# pc_ads1292r_brk_v3.net
KiCad netlist of a schematic drawn in EAGLE
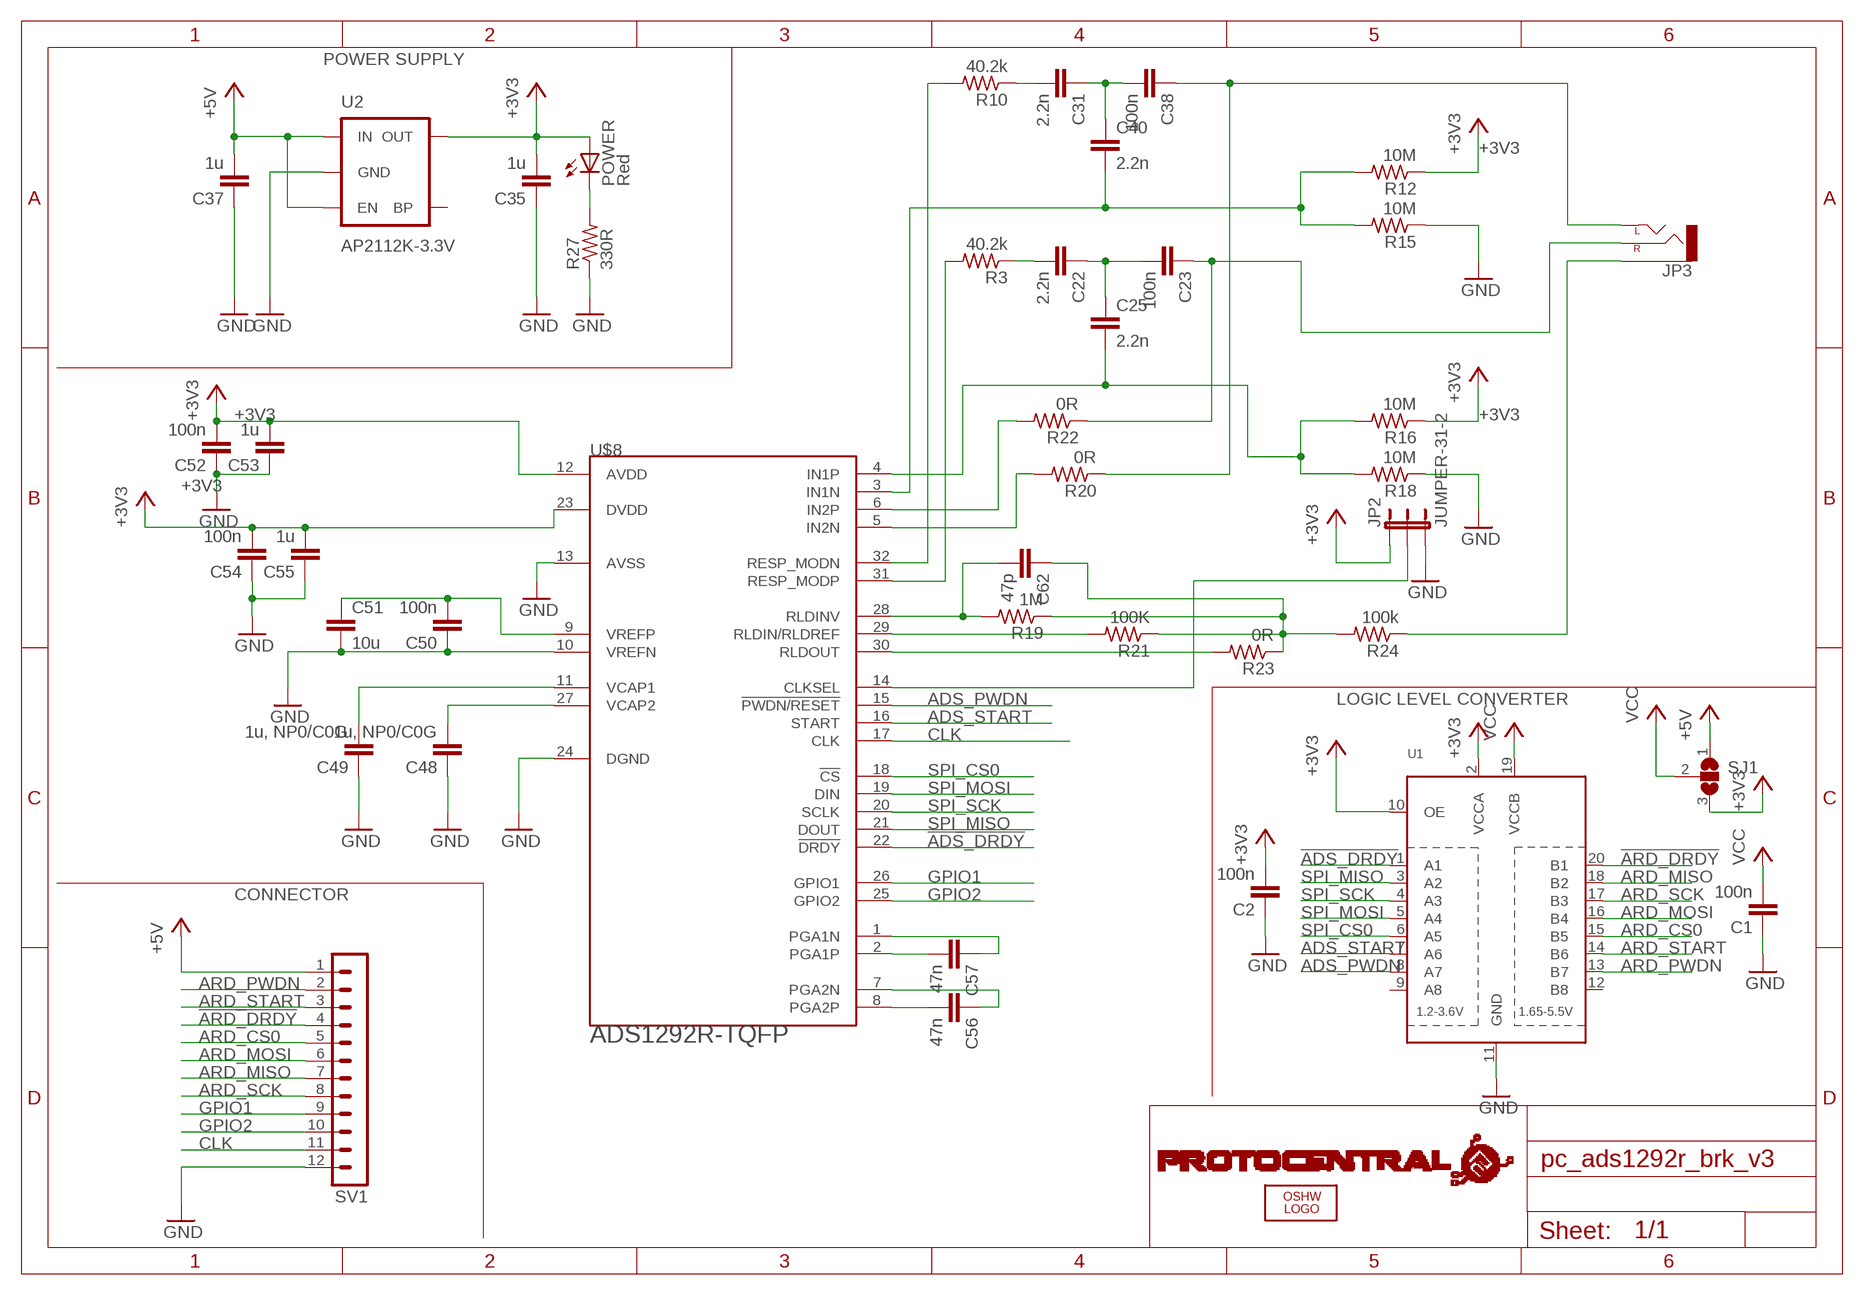
[diagram p0: schematic, sheet 1]

(export (version "E")
  (design (tool "Eeschema 10.0.6"))
  (components
    (comp (ref "C1")
      (value "100n")
      (footprint "eagle-import:C0402")
      (libsource (lib "eagle-import") (part "C-EUC0402"))
    )
    (comp (ref "C2")
      (value "100n")
      (footprint "eagle-import:C0402")
      (libsource (lib "eagle-import") (part "C-EUC0402"))
    )
    (comp (ref "C22")
      (value "2.2n")
      (footprint "eagle-import:C0402")
      (libsource (lib "eagle-import") (part "C-EUC0402"))
    )
    (comp (ref "C23")
      (value "100n")
      (footprint "eagle-import:C0402")
      (libsource (lib "eagle-import") (part "C-EUC0402"))
    )
    (comp (ref "C25")
      (value "2.2n")
      (footprint "eagle-import:C0402")
      (libsource (lib "eagle-import") (part "C-EUC0402"))
    )
    (comp (ref "C31")
      (value "2.2n")
      (footprint "eagle-import:C0402")
      (libsource (lib "eagle-import") (part "C-EUC0402"))
    )
    (comp (ref "C35")
      (value "1u")
      (footprint "eagle-import:C0402")
      (libsource (lib "eagle-import") (part "C-EUC0402"))
    )
    (comp (ref "C37")
      (value "1u")
      (footprint "eagle-import:C0402")
      (libsource (lib "eagle-import") (part "C-EUC0402"))
    )
    (comp (ref "C38")
      (value "100n")
      (footprint "eagle-import:C0402")
      (libsource (lib "eagle-import") (part "C-EUC0402"))
    )
    (comp (ref "C40")
      (value "2.2n")
      (footprint "eagle-import:C0402")
      (libsource (lib "eagle-import") (part "C-EUC0402"))
    )
    (comp (ref "C48")
      (value "1u, NP0/C0G")
      (footprint "eagle-import:C0402")
      (libsource (lib "eagle-import") (part "C-EUC0402"))
    )
    (comp (ref "C49")
      (value "1u, NP0/C0G")
      (footprint "eagle-import:C0402")
      (libsource (lib "eagle-import") (part "C-EUC0402"))
    )
    (comp (ref "C50")
      (value "100n")
      (footprint "eagle-import:C0402")
      (libsource (lib "eagle-import") (part "C-EUC0402"))
    )
    (comp (ref "C51")
      (value "10u")
      (footprint "eagle-import:C0603")
      (libsource (lib "eagle-import") (part "resistor_C-EUC0603"))
    )
    (comp (ref "C52")
      (value "100n")
      (footprint "eagle-import:C0402")
      (libsource (lib "eagle-import") (part "C-EUC0402"))
    )
    (comp (ref "C53")
      (value "1u")
      (footprint "eagle-import:C0402")
      (libsource (lib "eagle-import") (part "C-EUC0402"))
    )
    (comp (ref "C54")
      (value "100n")
      (footprint "eagle-import:C0402")
      (libsource (lib "eagle-import") (part "C-EUC0402"))
    )
    (comp (ref "C55")
      (value "1u")
      (footprint "eagle-import:C0402")
      (libsource (lib "eagle-import") (part "C-EUC0402"))
    )
    (comp (ref "C56")
      (value "47n")
      (footprint "eagle-import:C0402")
      (libsource (lib "eagle-import") (part "C-EUC0402"))
    )
    (comp (ref "C57")
      (value "47n")
      (footprint "eagle-import:C0402")
      (libsource (lib "eagle-import") (part "C-EUC0402"))
    )
    (comp (ref "C62")
      (value "47p")
      (footprint "eagle-import:C0402")
      (libsource (lib "eagle-import") (part "C-EUC0402"))
    )
    (comp (ref "JP2")
      (value "JUMPER-31-2")
      (footprint "eagle-import:SJ_3_PASTE1&2")
      (libsource (lib "eagle-import") (part "JUMPER-31-2"))
    )
    (comp (ref "JP3")
      (value "AUDIO-JACKSMD2")
      (footprint "eagle-import:AUDIO-JACK-3.5MM-SMD")
      (libsource (lib "eagle-import") (part "AUDIO-JACKSMD2"))
    )
    (comp (ref "LOGO1")
      (value "OSHW_LOGO_FILLX0100-NT")
      (footprint "eagle-import:OSHW_FILLX100_NOTEXT")
      (libsource (lib "eagle-import") (part "OSHW_LOGO_FILLX0100-NT"))
    )
    (comp (ref "POWER")
      (value "Red")
      (footprint "eagle-import:CHIPLED_0603")
      (libsource (lib "eagle-import") (part "LEDCHIPLED_0603"))
    )
    (comp (ref "R3")
      (value "40.2k")
      (footprint "eagle-import:R0402")
      (libsource (lib "eagle-import") (part "R-US_R0402"))
    )
    (comp (ref "R10")
      (value "40.2k")
      (footprint "eagle-import:R0402")
      (libsource (lib "eagle-import") (part "R-US_R0402"))
    )
    (comp (ref "R12")
      (value "10M")
      (footprint "eagle-import:R0402")
      (libsource (lib "eagle-import") (part "R-US_R0402"))
    )
    (comp (ref "R15")
      (value "10M")
      (footprint "eagle-import:R0402")
      (libsource (lib "eagle-import") (part "R-US_R0402"))
    )
    (comp (ref "R16")
      (value "10M")
      (footprint "eagle-import:R0402")
      (libsource (lib "eagle-import") (part "R-US_R0402"))
    )
    (comp (ref "R18")
      (value "10M")
      (footprint "eagle-import:R0402")
      (libsource (lib "eagle-import") (part "R-US_R0402"))
    )
    (comp (ref "R19")
      (value "1M")
      (footprint "eagle-import:R0402")
      (libsource (lib "eagle-import") (part "R-US_R0402"))
    )
    (comp (ref "R20")
      (value "0R")
      (footprint "eagle-import:R0402")
      (libsource (lib "eagle-import") (part "R-US_R0402"))
    )
    (comp (ref "R21")
      (value "100K")
      (footprint "eagle-import:R0402")
      (libsource (lib "eagle-import") (part "R-US_R0402"))
    )
    (comp (ref "R22")
      (value "0R")
      (footprint "eagle-import:R0402")
      (libsource (lib "eagle-import") (part "R-US_R0402"))
    )
    (comp (ref "R23")
      (value "0R")
      (footprint "eagle-import:R0402")
      (libsource (lib "eagle-import") (part "R-US_R0402"))
    )
    (comp (ref "R24")
      (value "100k")
      (footprint "eagle-import:R0402")
      (libsource (lib "eagle-import") (part "R-US_R0402"))
    )
    (comp (ref "R27")
      (value "330R")
      (footprint "eagle-import:R0402")
      (libsource (lib "eagle-import") (part "R-US_R0402"))
    )
    (comp (ref "SJ1")
      (value "SJ2W")
      (footprint "eagle-import:SJ_2")
      (libsource (lib "eagle-import") (part "SJ2W"))
    )
    (comp (ref "SV1")
      (value "MA12-1")
      (footprint "eagle-import:MA12-1")
      (libsource (lib "eagle-import") (part "MA12-1"))
    )
    (comp (ref "U$1")
      (value "PROTY-LOGO")
      (footprint "eagle-import:LOGO-PROTY")
      (libsource (lib "eagle-import") (part "PROTY-LOGO"))
    )
    (comp (ref "U$8")
      (value "ADS1292R-TQFP")
      (footprint "eagle-import:SQFP-S-5X5-32")
      (libsource (lib "eagle-import") (part "ADS1292R-TQFP"))
    )
    (comp (ref "U1")
      (value "TXB0108PWR")
      (footprint "eagle-import:TSSOP20")
      (libsource (lib "eagle-import") (part "TXB0108PWR"))
    )
    (comp (ref "U2")
      (value "AP2112K-3.3V")
      (footprint "eagle-import:SOT23-5")
      (libsource (lib "eagle-import") (part "V_REG_LDOSMD"))
    )
  )
  (nets
    (net (code "1") (name "+3V3") (class "Default")
      (node (ref "C2") (pin "2") (pinfunction "2_2") (pintype "passive"))
      (node (ref "C35") (pin "2") (pinfunction "2_2") (pintype "passive"))
      (node (ref "C52") (pin "2") (pinfunction "2_2") (pintype "passive"))
      (node (ref "C53") (pin "2") (pinfunction "2_2") (pintype "passive"))
      (node (ref "C54") (pin "2") (pinfunction "2_2") (pintype "passive"))
      (node (ref "C55") (pin "2") (pinfunction "2_2") (pintype "passive"))
      (node (ref "JP2") (pin "1") (pinfunction "1_1") (pintype "passive"))
      (node (ref "POWER") (pin "A") (pinfunction "A_A") (pintype "passive"))
      (node (ref "R12") (pin "1") (pinfunction "1_1") (pintype "passive"))
      (node (ref "R16") (pin "1") (pinfunction "1_1") (pintype "passive"))
      (node (ref "SJ1") (pin "3") (pinfunction "3_3") (pintype "passive"))
      (node (ref "U$8") (pin "12") (pinfunction "AVDD_12") (pintype "power_in"))
      (node (ref "U$8") (pin "23") (pinfunction "DVDD_23") (pintype "power_in"))
      (node (ref "U1") (pin "10") (pinfunction "OE_10") (pintype "bidirectional"))
      (node (ref "U1") (pin "2") (pinfunction "VCCA_2") (pintype "bidirectional"))
      (node (ref "U2") (pin "5") (pinfunction "OUT_5") (pintype "passive"))
    )
    (net (code "2") (name "+5V") (class "Default")
      (node (ref "C37") (pin "2") (pinfunction "2_2") (pintype "passive"))
      (node (ref "SJ1") (pin "1") (pinfunction "1_1") (pintype "passive"))
      (node (ref "SV1") (pin "1") (pinfunction "1_1") (pintype "passive"))
      (node (ref "U2") (pin "1") (pinfunction "IN_1") (pintype "input"))
      (node (ref "U2") (pin "3") (pinfunction "EN_3") (pintype "input"))
    )
    (net (code "3") (name "/ADS_PWDN") (class "Default")
      (node (ref "U$8") (pin "15") (pinfunction "~{PWDN/RESET}_15") (pintype "bidirectional"))
      (node (ref "U1") (pin "8") (pinfunction "A7_8") (pintype "bidirectional"))
    )
    (net (code "4") (name "/ADS_START") (class "Default")
      (node (ref "U$8") (pin "16") (pinfunction "START_16") (pintype "bidirectional"))
      (node (ref "U1") (pin "7") (pinfunction "A6_7") (pintype "bidirectional"))
    )
    (net (code "5") (name "/ARD_CS0") (class "Default")
      (node (ref "SV1") (pin "5") (pinfunction "5_5") (pintype "passive"))
      (node (ref "U1") (pin "15") (pinfunction "B5_15") (pintype "bidirectional"))
    )
    (net (code "6") (name "/ARD_MISO") (class "Default")
      (node (ref "SV1") (pin "7") (pinfunction "7_7") (pintype "passive"))
      (node (ref "U1") (pin "18") (pinfunction "B2_18") (pintype "bidirectional"))
    )
    (net (code "7") (name "/ARD_MOSI") (class "Default")
      (node (ref "SV1") (pin "6") (pinfunction "6_6") (pintype "passive"))
      (node (ref "U1") (pin "16") (pinfunction "B4_16") (pintype "bidirectional"))
    )
    (net (code "8") (name "/ARD_PWDN") (class "Default")
      (node (ref "SV1") (pin "2") (pinfunction "2_2") (pintype "passive"))
      (node (ref "U1") (pin "13") (pinfunction "B7_13") (pintype "bidirectional"))
    )
    (net (code "9") (name "/ARD_SCK") (class "Default")
      (node (ref "SV1") (pin "8") (pinfunction "8_8") (pintype "passive"))
      (node (ref "U1") (pin "17") (pinfunction "B3_17") (pintype "bidirectional"))
    )
    (net (code "10") (name "/ARD_START") (class "Default")
      (node (ref "SV1") (pin "3") (pinfunction "3_3") (pintype "passive"))
      (node (ref "U1") (pin "14") (pinfunction "B6_14") (pintype "bidirectional"))
    )
    (net (code "11") (name "/CLK") (class "Default")
      (node (ref "SV1") (pin "11") (pinfunction "11_11") (pintype "passive"))
      (node (ref "U$8") (pin "17") (pinfunction "CLK_17") (pintype "bidirectional"))
    )
    (net (code "12") (name "/GPIO1") (class "Default")
      (node (ref "SV1") (pin "9") (pinfunction "9_9") (pintype "passive"))
      (node (ref "U$8") (pin "26") (pinfunction "GPIO1_26") (pintype "bidirectional"))
    )
    (net (code "13") (name "/GPIO2") (class "Default")
      (node (ref "SV1") (pin "10") (pinfunction "10_10") (pintype "passive"))
      (node (ref "U$8") (pin "25") (pinfunction "GPIO2_25") (pintype "bidirectional"))
    )
    (net (code "14") (name "/SPI_CS0") (class "Default")
      (node (ref "U$8") (pin "18") (pinfunction "~{CS}_18") (pintype "bidirectional"))
      (node (ref "U1") (pin "6") (pinfunction "A5_6") (pintype "bidirectional"))
    )
    (net (code "15") (name "/SPI_MISO") (class "Default")
      (node (ref "U$8") (pin "21") (pinfunction "DOUT_21") (pintype "bidirectional"))
      (node (ref "U1") (pin "3") (pinfunction "A2_3") (pintype "bidirectional"))
    )
    (net (code "16") (name "/SPI_MOSI") (class "Default")
      (node (ref "U$8") (pin "19") (pinfunction "DIN_19") (pintype "bidirectional"))
      (node (ref "U1") (pin "5") (pinfunction "A4_5") (pintype "bidirectional"))
    )
    (net (code "17") (name "/SPI_SCK") (class "Default")
      (node (ref "U$8") (pin "20") (pinfunction "SCLK_20") (pintype "bidirectional"))
      (node (ref "U1") (pin "4") (pinfunction "A3_4") (pintype "bidirectional"))
    )
    (net (code "18") (name "/~{ADS_DRDY}") (class "Default")
      (node (ref "U$8") (pin "22") (pinfunction "~{DRDY}_22") (pintype "bidirectional"))
      (node (ref "U1") (pin "1") (pinfunction "A1_1") (pintype "bidirectional"))
    )
    (net (code "19") (name "/~{ARD_DRDY}") (class "Default")
      (node (ref "SV1") (pin "4") (pinfunction "4_4") (pintype "passive"))
      (node (ref "U1") (pin "20") (pinfunction "B1_20") (pintype "bidirectional"))
    )
    (net (code "20") (name "GND") (class "Default")
      (node (ref "C1") (pin "1") (pinfunction "1_1") (pintype "passive"))
      (node (ref "C2") (pin "1") (pinfunction "1_1") (pintype "passive"))
      (node (ref "C35") (pin "1") (pinfunction "1_1") (pintype "passive"))
      (node (ref "C37") (pin "1") (pinfunction "1_1") (pintype "passive"))
      (node (ref "C48") (pin "1") (pinfunction "1_1") (pintype "passive"))
      (node (ref "C49") (pin "1") (pinfunction "1_1") (pintype "passive"))
      (node (ref "C50") (pin "1") (pinfunction "1_1") (pintype "passive"))
      (node (ref "C51") (pin "2") (pinfunction "2_2") (pintype "passive"))
      (node (ref "C52") (pin "1") (pinfunction "1_1") (pintype "passive"))
      (node (ref "C53") (pin "1") (pinfunction "1_1") (pintype "passive"))
      (node (ref "C54") (pin "1") (pinfunction "1_1") (pintype "passive"))
      (node (ref "C55") (pin "1") (pinfunction "1_1") (pintype "passive"))
      (node (ref "JP2") (pin "3") (pinfunction "3_3") (pintype "passive"))
      (node (ref "R15") (pin "1") (pinfunction "1_1") (pintype "passive"))
      (node (ref "R18") (pin "1") (pinfunction "1_1") (pintype "passive"))
      (node (ref "R27") (pin "1") (pinfunction "1_1") (pintype "passive"))
      (node (ref "SV1") (pin "12") (pinfunction "12_12") (pintype "passive"))
      (node (ref "U$8") (pin "10") (pinfunction "VREFN_10") (pintype "bidirectional"))
      (node (ref "U$8") (pin "13") (pinfunction "AVSS_13") (pintype "bidirectional"))
      (node (ref "U$8") (pin "24") (pinfunction "DGND_24") (pintype "bidirectional"))
      (node (ref "U1") (pin "11") (pinfunction "GND_11") (pintype "bidirectional"))
      (node (ref "U2") (pin "2") (pinfunction "GND_2") (pintype "input"))
    )
    (net (code "21") (name "Net-(C22-Pad1)") (class "Default")
      (node (ref "C22") (pin "1") (pinfunction "1_1") (pintype "passive"))
      (node (ref "C23") (pin "2") (pinfunction "2_2") (pintype "passive"))
      (node (ref "C25") (pin "1") (pinfunction "1_1") (pintype "passive"))
    )
    (net (code "22") (name "Net-(C22-Pad2)") (class "Default")
      (node (ref "C22") (pin "2") (pinfunction "2_2") (pintype "passive"))
      (node (ref "R3") (pin "1") (pinfunction "1_1") (pintype "passive"))
    )
    (net (code "23") (name "Net-(C31-Pad1)") (class "Default")
      (node (ref "C31") (pin "1") (pinfunction "1_1") (pintype "passive"))
      (node (ref "C38") (pin "2") (pinfunction "2_2") (pintype "passive"))
      (node (ref "C40") (pin "1") (pinfunction "1_1") (pintype "passive"))
    )
    (net (code "24") (name "Net-(C31-Pad2)") (class "Default")
      (node (ref "C31") (pin "2") (pinfunction "2_2") (pintype "passive"))
      (node (ref "R10") (pin "1") (pinfunction "1_1") (pintype "passive"))
    )
    (net (code "25") (name "Net-(C62-Pad1)") (class "Default")
      (node (ref "C62") (pin "1") (pinfunction "1_1") (pintype "passive"))
      (node (ref "R19") (pin "1") (pinfunction "1_1") (pintype "passive"))
      (node (ref "R21") (pin "1") (pinfunction "1_1") (pintype "passive"))
      (node (ref "R23") (pin "1") (pinfunction "1_1") (pintype "passive"))
      (node (ref "R24") (pin "2") (pinfunction "2_2") (pintype "passive"))
    )
    (net (code "26") (name "Net-(JP3-LEFT)") (class "Default")
      (node (ref "C38") (pin "1") (pinfunction "1_1") (pintype "passive"))
      (node (ref "JP3") (pin "TIP") (pinfunction "LEFT_TIP") (pintype "bidirectional"))
      (node (ref "R20") (pin "1") (pinfunction "1_1") (pintype "passive"))
    )
    (net (code "27") (name "Net-(JP3-PadSLEEVE)") (class "Default")
      (node (ref "JP3") (pin "SLEEVE") (pinfunction "SLEEVE_SLEEVE") (pintype "bidirectional"))
      (node (ref "R24") (pin "1") (pinfunction "1_1") (pintype "passive"))
    )
    (net (code "28") (name "Net-(JP3-RIGHT)") (class "Default")
      (node (ref "C23") (pin "1") (pinfunction "1_1") (pintype "passive"))
      (node (ref "JP3") (pin "RING") (pinfunction "RIGHT_RING") (pintype "bidirectional"))
      (node (ref "R22") (pin "1") (pinfunction "1_1") (pintype "passive"))
    )
    (net (code "29") (name "Net-(POWER-PadC)") (class "Default")
      (node (ref "POWER") (pin "C") (pinfunction "C_C") (pintype "passive"))
      (node (ref "R27") (pin "2") (pinfunction "2_2") (pintype "passive"))
    )
    (net (code "30") (name "Net-(U$8-CLKSEL)") (class "Default")
      (node (ref "JP2") (pin "2") (pinfunction "2_2") (pintype "passive"))
      (node (ref "U$8") (pin "14") (pinfunction "CLKSEL_14") (pintype "bidirectional"))
    )
    (net (code "31") (name "Net-(U$8-IN1N)") (class "Default")
      (node (ref "C40") (pin "2") (pinfunction "2_2") (pintype "passive"))
      (node (ref "R12") (pin "2") (pinfunction "2_2") (pintype "passive"))
      (node (ref "R15") (pin "2") (pinfunction "2_2") (pintype "passive"))
      (node (ref "U$8") (pin "3") (pinfunction "IN1N_3") (pintype "input"))
    )
    (net (code "32") (name "Net-(U$8-IN1P)") (class "Default")
      (node (ref "C25") (pin "2") (pinfunction "2_2") (pintype "passive"))
      (node (ref "R16") (pin "2") (pinfunction "2_2") (pintype "passive"))
      (node (ref "R18") (pin "2") (pinfunction "2_2") (pintype "passive"))
      (node (ref "U$8") (pin "4") (pinfunction "IN1P_4") (pintype "input"))
    )
    (net (code "33") (name "Net-(U$8-IN2N)") (class "Default")
      (node (ref "R20") (pin "2") (pinfunction "2_2") (pintype "passive"))
      (node (ref "U$8") (pin "5") (pinfunction "IN2N_5") (pintype "input"))
    )
    (net (code "34") (name "Net-(U$8-IN2P)") (class "Default")
      (node (ref "R22") (pin "2") (pinfunction "2_2") (pintype "passive"))
      (node (ref "U$8") (pin "6") (pinfunction "IN2P_6") (pintype "input"))
    )
    (net (code "35") (name "Net-(U$8-PGA1N)") (class "Default")
      (node (ref "C57") (pin "1") (pinfunction "1_1") (pintype "passive"))
      (node (ref "U$8") (pin "1") (pinfunction "PGA1N_1") (pintype "bidirectional"))
    )
    (net (code "36") (name "Net-(U$8-PGA1P)") (class "Default")
      (node (ref "C57") (pin "2") (pinfunction "2_2") (pintype "passive"))
      (node (ref "U$8") (pin "2") (pinfunction "PGA1P_2") (pintype "bidirectional"))
    )
    (net (code "37") (name "Net-(U$8-PGA2N)") (class "Default")
      (node (ref "C56") (pin "1") (pinfunction "1_1") (pintype "passive"))
      (node (ref "U$8") (pin "7") (pinfunction "PGA2N_7") (pintype "bidirectional"))
    )
    (net (code "38") (name "Net-(U$8-PGA2P)") (class "Default")
      (node (ref "C56") (pin "2") (pinfunction "2_2") (pintype "passive"))
      (node (ref "U$8") (pin "8") (pinfunction "PGA2P_8") (pintype "bidirectional"))
    )
    (net (code "39") (name "Net-(U$8-RESP_MODN)") (class "Default")
      (node (ref "R10") (pin "2") (pinfunction "2_2") (pintype "passive"))
      (node (ref "U$8") (pin "32") (pinfunction "RESP_MODN_32") (pintype "bidirectional"))
    )
    (net (code "40") (name "Net-(U$8-RESP_MODP)") (class "Default")
      (node (ref "R3") (pin "2") (pinfunction "2_2") (pintype "passive"))
      (node (ref "U$8") (pin "31") (pinfunction "RESP_MODP_31") (pintype "bidirectional"))
    )
    (net (code "41") (name "Net-(U$8-RLDINV)") (class "Default")
      (node (ref "C62") (pin "2") (pinfunction "2_2") (pintype "passive"))
      (node (ref "R19") (pin "2") (pinfunction "2_2") (pintype "passive"))
      (node (ref "U$8") (pin "28") (pinfunction "RLDINV_28") (pintype "bidirectional"))
    )
    (net (code "42") (name "Net-(U$8-RLDIN{slash}RLDREF)") (class "Default")
      (node (ref "R21") (pin "2") (pinfunction "2_2") (pintype "passive"))
      (node (ref "U$8") (pin "29") (pinfunction "RLDIN/RLDREF_29") (pintype "bidirectional"))
    )
    (net (code "43") (name "Net-(U$8-RLDOUT)") (class "Default")
      (node (ref "R23") (pin "2") (pinfunction "2_2") (pintype "passive"))
      (node (ref "U$8") (pin "30") (pinfunction "RLDOUT_30") (pintype "bidirectional"))
    )
    (net (code "44") (name "Net-(U$8-VCAP1)") (class "Default")
      (node (ref "C49") (pin "2") (pinfunction "2_2") (pintype "passive"))
      (node (ref "U$8") (pin "11") (pinfunction "VCAP1_11") (pintype "bidirectional"))
    )
    (net (code "45") (name "Net-(U$8-VCAP2)") (class "Default")
      (node (ref "C48") (pin "2") (pinfunction "2_2") (pintype "passive"))
      (node (ref "U$8") (pin "27") (pinfunction "VCAP2_27") (pintype "bidirectional"))
    )
    (net (code "46") (name "Net-(U$8-VREFP)") (class "Default")
      (node (ref "C50") (pin "2") (pinfunction "2_2") (pintype "passive"))
      (node (ref "C51") (pin "1") (pinfunction "1_1") (pintype "passive"))
      (node (ref "U$8") (pin "9") (pinfunction "VREFP_9") (pintype "bidirectional"))
    )
    (net (code "47") (name "VCC") (class "Default")
      (node (ref "C1") (pin "2") (pinfunction "2_2") (pintype "passive"))
      (node (ref "SJ1") (pin "2") (pinfunction "2_2") (pintype "passive"))
      (node (ref "U1") (pin "19") (pinfunction "VCCB_19") (pintype "bidirectional"))
    )
    (net (code "48") (name "unconnected-(U1-A8-Pad9)") (class "Default")
      (node (ref "U1") (pin "9") (pinfunction "A8_9") (pintype "bidirectional"))
    )
    (net (code "49") (name "unconnected-(U1-B8-Pad12)") (class "Default")
      (node (ref "U1") (pin "12") (pinfunction "B8_12") (pintype "bidirectional"))
    )
    (net (code "50") (name "unconnected-(U2-BP-Pad4)") (class "Default")
      (node (ref "U2") (pin "4") (pinfunction "BP_4") (pintype "input"))
    )
  )
)
